# Hahnentrittstulpe.net
KiCad netlist of a schematic drawn in EAGLE
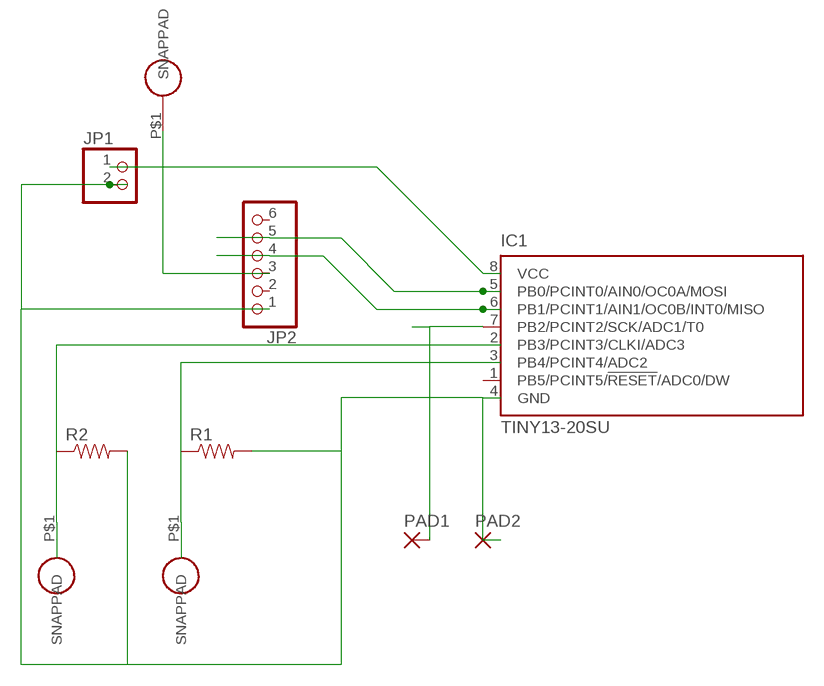
[diagram p0: schematic, sheet 1]

(export (version "E")
  (design (tool "Eeschema 10.0.6"))
  (components
    (comp (ref "IC1")
      (value "TINY13-20SU")
      (footprint "eagle-import:8S2")
      (fields (field (name "MPN") "ATTINY13-20SU"))
      (libsource (lib "eagle-import") (part "TINY13SU-20"))
    )
    (comp (ref "JP1")
      (value "PINHD-1X2")
      (footprint "eagle-import:1X02")
      (libsource (lib "eagle-import") (part "PINHD-1X2"))
    )
    (comp (ref "JP2")
      (value "PINHD-1X6/90")
      (footprint "eagle-import:1X06_90")
      (libsource (lib "eagle-import") (part "PINHD-1X6/90"))
    )
    (comp (ref "PAD1")
      (value "SMD2")
      (footprint "eagle-import:SMD1,27-2,54")
      (libsource (lib "eagle-import") (part "SMD2"))
    )
    (comp (ref "PAD2")
      (value "SMD2")
      (footprint "eagle-import:SMD1,27-2,54")
      (libsource (lib "eagle-import") (part "SMD2"))
    )
    (comp (ref "R1")
      (value "RESISTOR0805-RES")
      (footprint "eagle-import:0805")
      (libsource (lib "eagle-import") (part "RESISTOR0805-RES"))
    )
    (comp (ref "R2")
      (value "RESISTOR0805-RES")
      (footprint "eagle-import:0805")
      (libsource (lib "eagle-import") (part "RESISTOR0805-RES"))
    )
    (comp (ref "U$1")
      (value "SNAP-PAD_7MM_ROUND")
      (footprint "eagle-import:SNAP-PAD_7MM_RD")
      (libsource (lib "eagle-import") (part "SNAP-PAD_7MM_ROUND"))
    )
    (comp (ref "U$2")
      (value "SNAP-PAD_7MM_ROUND")
      (footprint "eagle-import:SNAP-PAD_7MM_RD")
      (libsource (lib "eagle-import") (part "SNAP-PAD_7MM_ROUND"))
    )
    (comp (ref "U$3")
      (value "SNAP-PAD_7MM_ROUND")
      (footprint "eagle-import:SNAP-PAD_7MM_RD")
      (libsource (lib "eagle-import") (part "SNAP-PAD_7MM_ROUND"))
    )
  )
  (nets
    (net (code "1") (name "Net-(IC1-GND)") (class "Default")
      (node (ref "IC1") (pin "4") (pinfunction "GND_4") (pintype "power_in"))
      (node (ref "JP1") (pin "2") (pinfunction "2_2") (pintype "passive"))
      (node (ref "JP2") (pin "1") (pinfunction "1_1") (pintype "passive"))
      (node (ref "PAD2") (pin "1") (pinfunction "P_1") (pintype "passive"))
      (node (ref "R1") (pin "2") (pinfunction "2_2") (pintype "passive"))
      (node (ref "R2") (pin "2") (pinfunction "2_2") (pintype "passive"))
    )
    (net (code "2") (name "Net-(IC1-PB0{slash}PCINT0{slash}AIN0{slash}OC0A{slash}MOSI)") (class "Default")
      (node (ref "IC1") (pin "5") (pinfunction "PB0/PCINT0/AIN0/OC0A/MOSI_5") (pintype "bidirectional"))
      (node (ref "JP2") (pin "5") (pinfunction "5_5") (pintype "passive"))
    )
    (net (code "3") (name "Net-(IC1-PB1{slash}PCINT1{slash}AIN1{slash}OC0B{slash}INT0{slash}MISO)") (class "Default")
      (node (ref "IC1") (pin "6") (pinfunction "PB1/PCINT1/AIN1/OC0B/INT0/MISO_6") (pintype "bidirectional"))
      (node (ref "JP2") (pin "4") (pinfunction "4_4") (pintype "passive"))
    )
    (net (code "4") (name "Net-(IC1-PB2{slash}PCINT2{slash}SCK{slash}ADC1{slash}T0)") (class "Default")
      (node (ref "IC1") (pin "7") (pinfunction "PB2/PCINT2/SCK/ADC1/T0_7") (pintype "bidirectional"))
      (node (ref "PAD1") (pin "1") (pinfunction "P_1") (pintype "passive"))
    )
    (net (code "5") (name "Net-(IC1-PB3{slash}PCINT3{slash}CLKI{slash}ADC3)") (class "Default")
      (node (ref "IC1") (pin "2") (pinfunction "PB3/PCINT3/CLKI/ADC3_2") (pintype "bidirectional"))
      (node (ref "R2") (pin "1") (pinfunction "1_1") (pintype "passive"))
      (node (ref "U$2") (pin "P$1") (pinfunction "SNAPPAD_P$1") (pintype "bidirectional"))
    )
    (net (code "6") (name "Net-(IC1-PB4{slash}PCINT4{slash}ADC2)") (class "Default")
      (node (ref "IC1") (pin "3") (pinfunction "PB4/PCINT4/ADC2_3") (pintype "bidirectional"))
      (node (ref "R1") (pin "1") (pinfunction "1_1") (pintype "passive"))
      (node (ref "U$1") (pin "P$1") (pinfunction "SNAPPAD_P$1") (pintype "bidirectional"))
    )
    (net (code "7") (name "Net-(IC1-VCC)") (class "Default")
      (node (ref "IC1") (pin "8") (pinfunction "VCC_8") (pintype "power_in"))
      (node (ref "JP1") (pin "1") (pinfunction "1_1") (pintype "passive"))
      (node (ref "JP2") (pin "3") (pinfunction "3_3") (pintype "passive"))
      (node (ref "U$3") (pin "P$1") (pinfunction "SNAPPAD_P$1") (pintype "bidirectional"))
    )
    (net (code "8") (name "unconnected-(IC1-PB5{slash}PCINT5{slash}~{RESET}{slash}ADC0{slash}DW-Pad1)") (class "Default")
      (node (ref "IC1") (pin "1") (pinfunction "PB5/PCINT5/~{RESET}/ADC0/DW_1") (pintype "bidirectional"))
    )
    (net (code "9") (name "unconnected-(JP2-Pad2)") (class "Default")
      (node (ref "JP2") (pin "2") (pinfunction "2_2") (pintype "passive"))
    )
    (net (code "10") (name "unconnected-(JP2-Pad6)") (class "Default")
      (node (ref "JP2") (pin "6") (pinfunction "6_6") (pintype "passive"))
    )
  )
)
